# Sheet1.net
KiCad netlist of a schematic drawn in Altium Designer
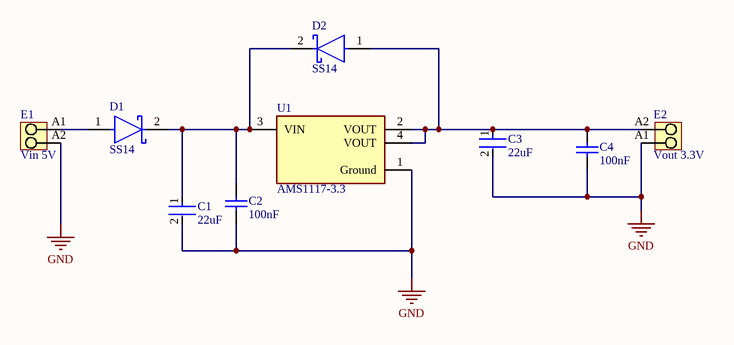
[diagram p0: Sheet1.SchDoc]

(export (version "E")
  (design (tool "Eeschema 10.0.6"))
  (components
    (comp (ref "C1")
      (value "22uF")
      (footprint "FP-C3225-250-0_4-IPC_C")
      (description "Multilayer Ceramic Capacitors 22uF ±20% 25V X7R SMD 1210")
      (libsource (lib "tụ ceramic 22 µF 25 V 1210 X7R") (part "CMP-08246-001769-2"))
    )
    (comp (ref "C2")
      (value "100nF")
      (footprint "CAPC0805(2012)100_N")
      (description "CAP 100nF 50V ±5% 0805 (2012 Metric) Thickness 1mm SMD")
      (fields (field (name "TOLERANCE") "Â±5%"))
      (libsource (lib "0,1uF 50V 0805") (part "CMP-1036-04418-1"))
    )
    (comp (ref "C3")
      (value "22uF")
      (footprint "FP-C3225-250-0_4-IPC_C")
      (description "Multilayer Ceramic Capacitors 22uF ±20% 25V X7R SMD 1210")
      (libsource (lib "tụ ceramic 22 µF 25 V 1210 X7R") (part "CMP-08246-001769-2"))
    )
    (comp (ref "C4")
      (value "100nF")
      (footprint "CAPC0805(2012)100_N")
      (description "CAP 100nF 50V ±5% 0805 (2012 Metric) Thickness 1mm SMD")
      (fields (field (name "TOLERANCE") "Â±5%"))
      (libsource (lib "0,1uF 50V 0805") (part "CMP-1036-04418-1"))
    )
    (comp (ref "D1")
      (value "SS14")
      (footprint "FP-403AE-MFG")
      (description "DIODE SCHOTTKY 40V 1A SMA")
      (fields
        (field (name "MANUFACTURER") "ON Semiconductor")
        (field (name "OCTOPART") "https://octopart.com/ss14-on+semiconductor-29205033")
      )
      (libsource (lib "diode ss14 do-214AC") (part "CMP-2000-04943-2"))
    )
    (comp (ref "D2")
      (value "SS14")
      (footprint "FP-403AE-MFG")
      (description "DIODE SCHOTTKY 40V 1A SMA")
      (fields
        (field (name "MANUFACTURER") "ON Semiconductor")
        (field (name "OCTOPART") "https://octopart.com/ss14-on+semiconductor-29205033")
      )
      (libsource (lib "diode ss14 do-214AC") (part "CMP-2000-04943-2"))
    )
    (comp (ref "E1")
      (value "Vin 5V")
      (footprint "LPP_5_08_90_02")
      (description "OMNIMATE Signal - series LP")
      (fields (field (name "PARTNUMBER") "1594400000") (field (name "MANUFACTURER") "Weidmueller"))
      (libsource (lib "") (part "CMP-1559-02057-1_1"))
    )
    (comp (ref "E2")
      (value "Vout 3.3V")
      (footprint "LPP_5_08_90_02")
      (description "OMNIMATE Signal - series LP")
      (fields (field (name "PARTNUMBER") "1594400000") (field (name "MANUFACTURER") "Weidmueller"))
      (libsource (lib "terminal block 2 pos 5,08mm") (part "CMP-1559-02057-1"))
    )
    (comp (ref "U1")
      (value "AMS1117-3.3")
      (footprint "FP-AMS1117-IPC_A")
      (description "LDO Voltage Regulators 1A, 3.3V")
      (fields
        (field (name "OCTOPART") "https://octopart.com/ams1117-3.3-advanced+monolithic+systems-25899300")
        (field (name "MANUFACTURER") "Advanced Monolithic Systems")
      )
      (libsource (lib "Components - 07.07.26 - 15.47") (part "CMP-209535-000001-1"))
    )
  )
  (nets
    (net (code "1") (name "GND") (class "Default")
      (node (ref "C1") (pin "2") (pinfunction "2_2") (pintype "passive"))
      (node (ref "C2") (pin "1") (pinfunction "1_1") (pintype "passive"))
      (node (ref "C3") (pin "2") (pinfunction "2_2") (pintype "passive"))
      (node (ref "C4") (pin "1") (pinfunction "1_1") (pintype "passive"))
      (node (ref "E1") (pin "A2") (pinfunction "A2_A2") (pintype "passive"))
      (node (ref "E2") (pin "A1") (pinfunction "A1_A1") (pintype "passive"))
      (node (ref "U1") (pin "1") (pinfunction "Ground_1") (pintype "power_in"))
    )
    (net (code "2") (name "Net-(D1-A)") (class "Default")
      (node (ref "D1") (pin "1") (pinfunction "A_1") (pintype "passive"))
      (node (ref "E1") (pin "A1") (pinfunction "A1_A1") (pintype "passive"))
    )
    (net (code "3") (name "Net-(D1-C)") (class "Default")
      (node (ref "C1") (pin "1") (pinfunction "1_1") (pintype "passive"))
      (node (ref "C2") (pin "2") (pinfunction "2_2") (pintype "passive"))
      (node (ref "D1") (pin "2") (pinfunction "C_2") (pintype "passive"))
      (node (ref "D2") (pin "2") (pinfunction "C_2") (pintype "passive"))
      (node (ref "U1") (pin "3") (pinfunction "VIN_3") (pintype "power_in"))
    )
    (net (code "4") (name "Net-(D2-A)") (class "Default")
      (node (ref "C3") (pin "1") (pinfunction "1_1") (pintype "passive"))
      (node (ref "C4") (pin "2") (pinfunction "2_2") (pintype "passive"))
      (node (ref "D2") (pin "1") (pinfunction "A_1") (pintype "passive"))
      (node (ref "E2") (pin "A2") (pinfunction "A2_A2") (pintype "passive"))
      (node (ref "U1") (pin "2") (pinfunction "VOUT_2") (pintype "passive"))
      (node (ref "U1") (pin "4") (pinfunction "VOUT_4") (pintype "passive"))
    )
  )
)
